# MainSch.net
KiCad netlist of a schematic drawn in Altium Designer
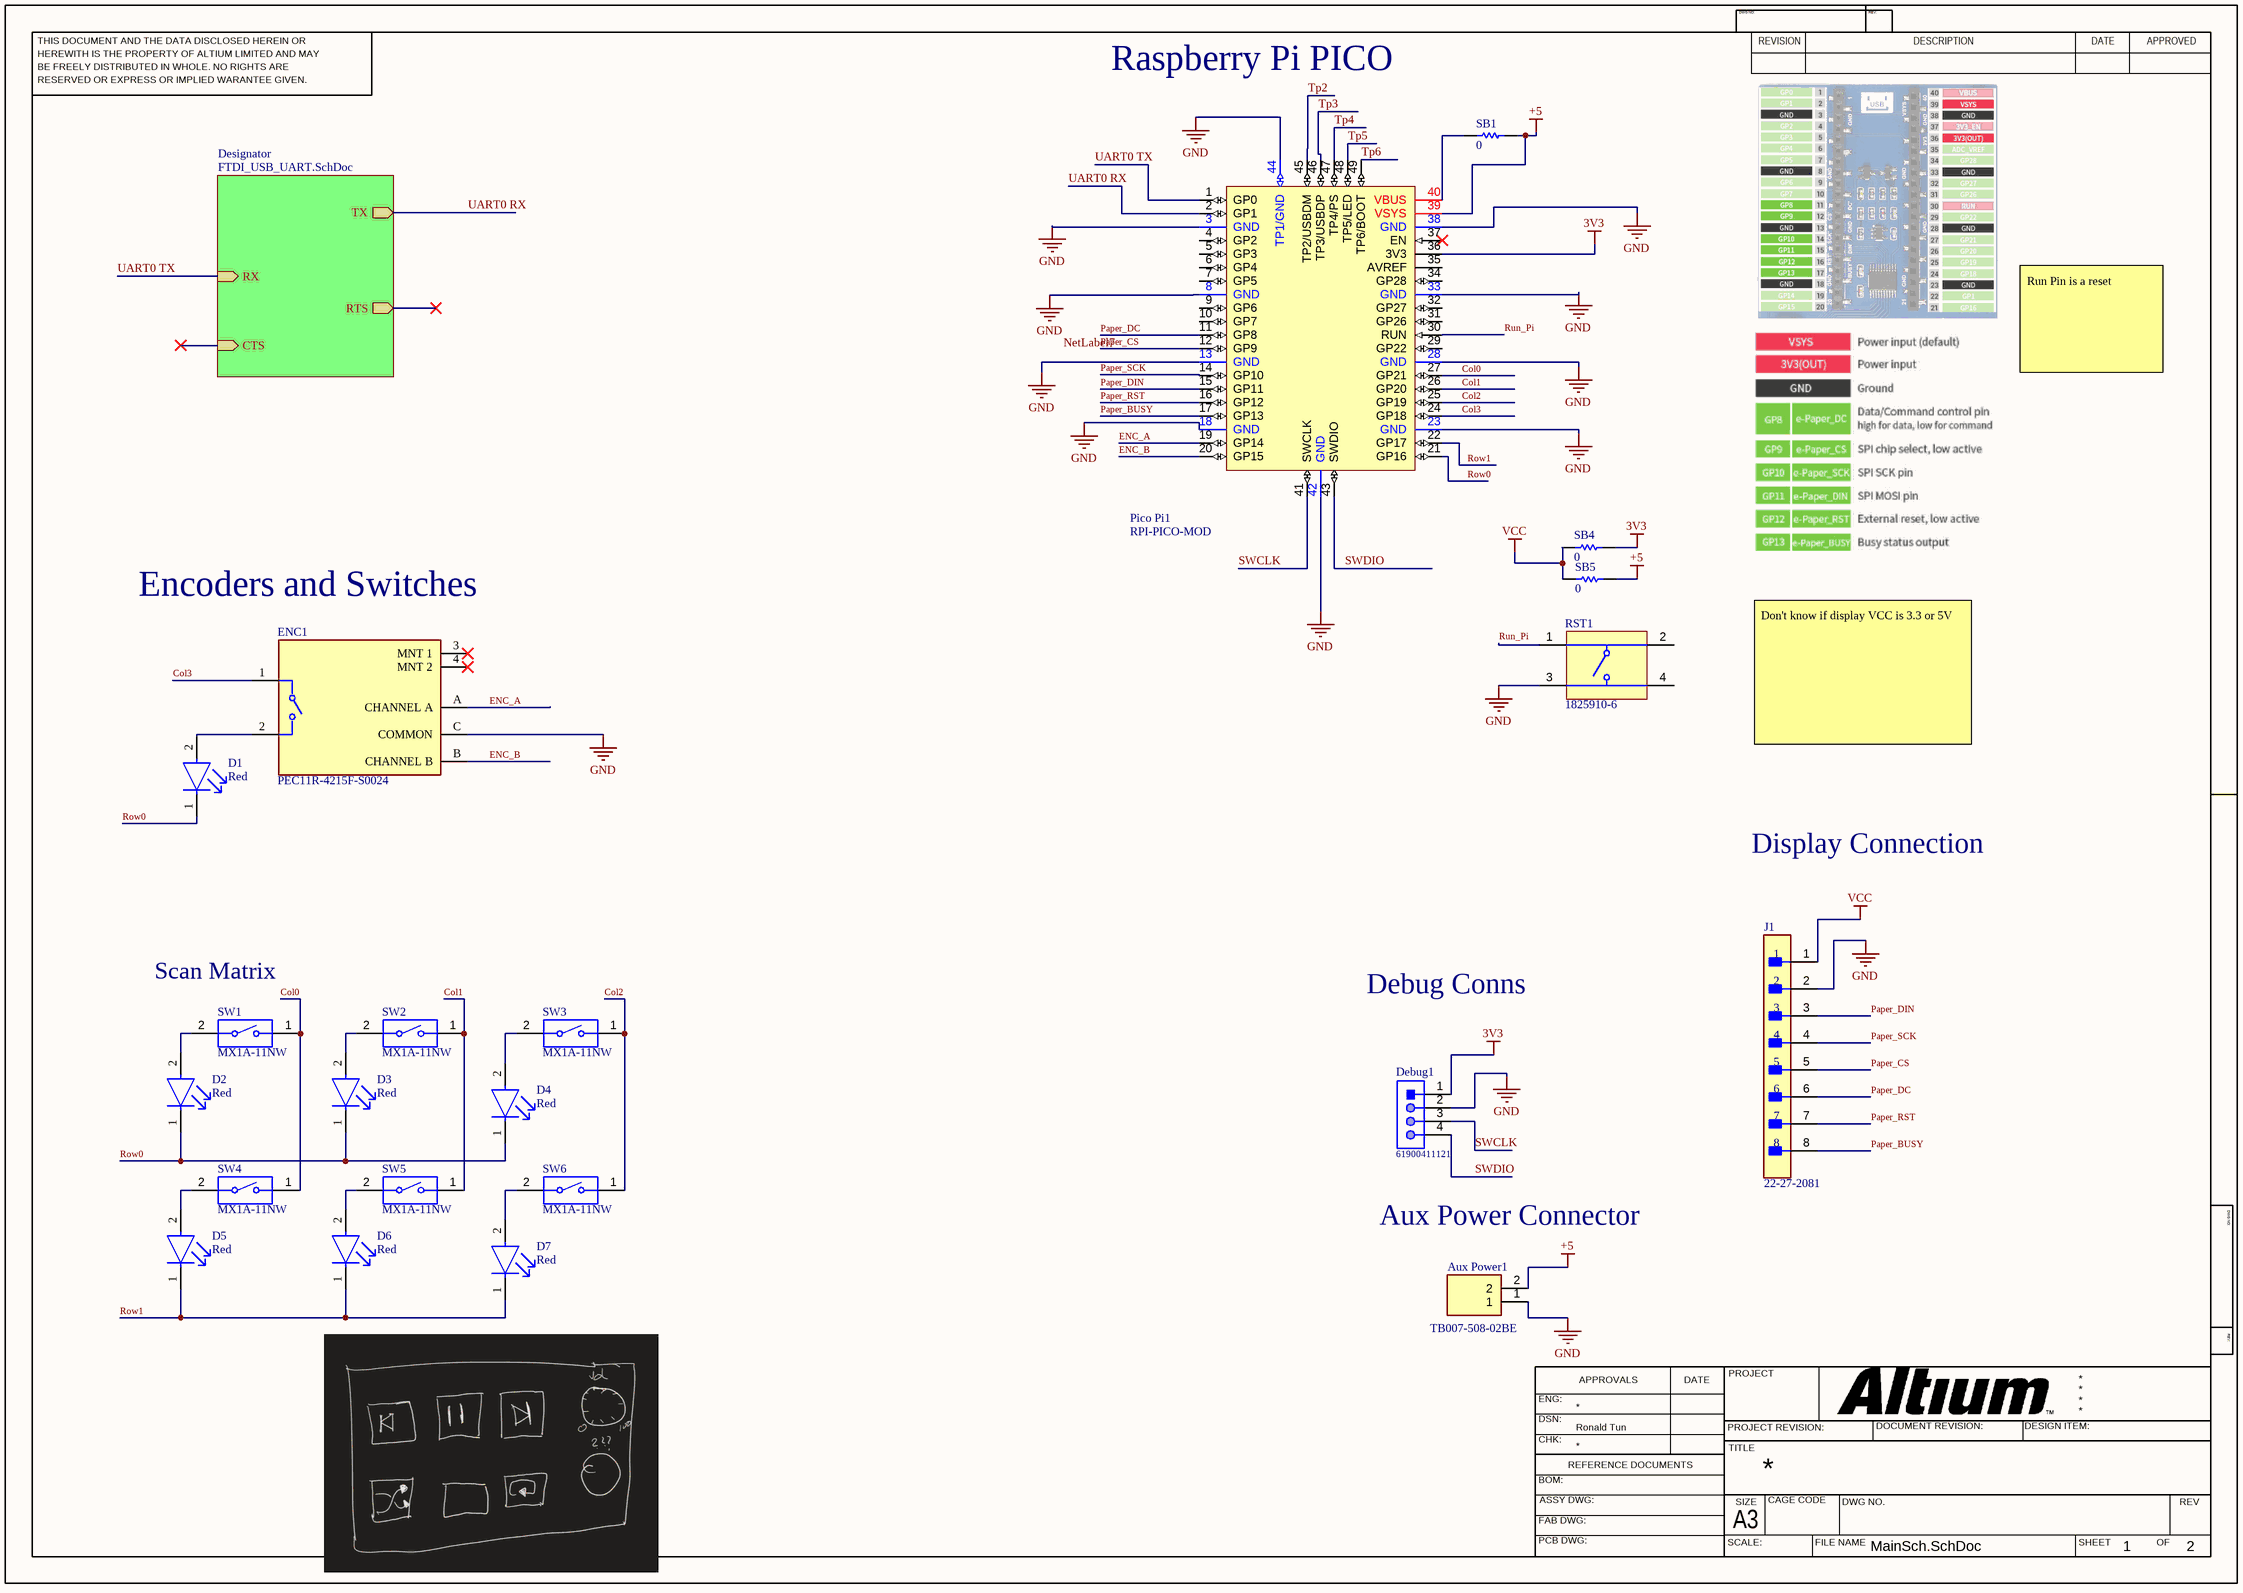
[diagram p0: MainSch.SchDoc]

(export (version "E")
  (design (tool "Eeschema 10.0.6"))
  (components
    (comp (ref "Aux Power1")
      (value "TB007-508-02BE")
      (footprint "SamacSys:TB00750802BE")
      (description "Connector")
      (fields (field (name "MOUSER PART NUMBER") "490-TB007-508-02BE"))
      (libsource (lib "SamacSys") (part "TB007-508-02BE"))
    )
    (comp (ref "D1")
      (value "Red")
      (footprint "FP-150080SS75000-MFG")
      (description "LED RED CLEAR 0805 SMD")
      (libsource (lib "Altium Content Vault") (part "8706943c75ba83719d021d2fdc84c58"))
    )
    (comp (ref "D2")
      (value "Red")
      (footprint "FP-150080SS75000-MFG")
      (description "LED RED CLEAR 0805 SMD")
      (libsource (lib "Altium Content Vault") (part "8706943c75ba83719d021d2fdc84c58"))
    )
    (comp (ref "D3")
      (value "Red")
      (footprint "FP-150080SS75000-MFG")
      (description "LED RED CLEAR 0805 SMD")
      (libsource (lib "Altium Content Vault") (part "8706943c75ba83719d021d2fdc84c58"))
    )
    (comp (ref "D4")
      (value "Red")
      (footprint "FP-150080SS75000-MFG")
      (description "LED RED CLEAR 0805 SMD")
      (libsource (lib "Altium Content Vault") (part "8706943c75ba83719d021d2fdc84c58"))
    )
    (comp (ref "D5")
      (value "Red")
      (footprint "FP-150080SS75000-MFG")
      (description "LED RED CLEAR 0805 SMD")
      (libsource (lib "Altium Content Vault") (part "8706943c75ba83719d021d2fdc84c58"))
    )
    (comp (ref "D6")
      (value "Red")
      (footprint "FP-150080SS75000-MFG")
      (description "LED RED CLEAR 0805 SMD")
      (libsource (lib "Altium Content Vault") (part "8706943c75ba83719d021d2fdc84c58"))
    )
    (comp (ref "D7")
      (value "Red")
      (footprint "FP-150080SS75000-MFG")
      (description "LED RED CLEAR 0805 SMD")
      (libsource (lib "Altium Content Vault") (part "8706943c75ba83719d021d2fdc84c58"))
    )
    (comp (ref "Debug1")
      (value "61900411121")
      (footprint "61900411121")
      (description "Male Locking Header WR-WTB, THT, Vertical, pitch 2.54 mm, 1 x 4 position")
      (fields (field (name "MANUFACTURER") "Wurth Elektronik") (field (name "PUBLISHER") "WurthElektronik"))
      (libsource (lib "Altium Content Vault") (part "WE-CN-1P-M-R4"))
    )
    (comp (ref "ENC1")
      (value "PEC11R-4215F-S0024")
      (footprint "FP-PEC11R-4215F-S0024-MFG")
      (description "ROTARY ENCODER MECHANICAL 24PPR")
      (libsource (lib "Altium Content Vault") (part "5f1dd25a4c49fa66e7eeb899730fe11"))
    )
    (comp (ref "J1")
      (value "22-27-2081")
      (footprint "FP-22-27-2081-MFG")
      (description "CONN HEADER VERT 8POS 2.54MM")
      (libsource (lib "Altium Content Vault") (part "99ec2b232beb5d2356d4d77f6a047f0"))
    )
    (comp (ref "Pico Pi1")
      (value "RPI-PICO-MOD")
      (footprint "RPI-PICO-MOD")
      (description "RASPBERRY PI PICO RP2040 BOARD")
      (fields
        (field (name "MANUFACTURER") "Raspberry Pi Foundation")
        (field (name "MANUFACTURER PART NO") "SC0915")
      )
      (libsource (lib "RPi_Pico") (part "RPI-PICO-MOD"))
    )
    (comp (ref "RST1")
      (value "1825910-6")
      (footprint "TECO-1825910-6_V")
      (description "Tact Switch, SPST-NO, 0.05 A, -35 to 85 degC, 4-Pin THD, RoHS, Bulk")
      (fields (field (name "MANUFACTURER") "TE Connectivity"))
      (libsource (lib "Altium Content Vault") (part "SW-SPST-4_A"))
    )
    (comp (ref "SB1")
      (value "0")
      (footprint "RESC1608X55X25ML10T15")
      (description "Chip Resistor, 0 Ohm, +/- 5%, 0.1 W, -55 to 155 degC, 0603 (1608 Metric), RoHS, Tape and Reel")
      (fields (field (name "TOLERANCE") "5%") (field (name "MANUFACTURER") "Yageo"))
      (libsource (lib "Altium Content Vault") (part "RES-2"))
    )
    (comp (ref "SB4")
      (value "0")
      (footprint "RESC1608X55X25ML10T15")
      (description "Chip Resistor, 0 Ohm, +/- 5%, 0.1 W, -55 to 155 degC, 0603 (1608 Metric), RoHS, Tape and Reel")
      (fields (field (name "TOLERANCE") "5%") (field (name "MANUFACTURER") "Yageo"))
      (libsource (lib "Altium Content Vault") (part "RES-2"))
    )
    (comp (ref "SB5")
      (value "0")
      (footprint "RESC1608X55X25ML10T15")
      (description "Chip Resistor, 0 Ohm, +/- 5%, 0.1 W, -55 to 155 degC, 0603 (1608 Metric), RoHS, Tape and Reel")
      (fields (field (name "TOLERANCE") "5%") (field (name "MANUFACTURER") "Yageo"))
      (libsource (lib "Altium Content Vault") (part "RES-2"))
    )
    (comp (ref "SW1")
      (value "MX1A-11NW")
      (footprint "CHRY-MX1A-11NW_V")
      (description "Keylock Switch, 12 V, -10 to 70 degC, 2-Pin THD, RoHS, Bulk")
      (fields (field (name "MANUFACTURER") "Cherry") (field (name "PART NO") "MX1A11NW"))
      (libsource (lib "Altium Content Vault") (part "KEYSW-SPST-2"))
    )
    (comp (ref "SW2")
      (value "MX1A-11NW")
      (footprint "CHRY-MX1A-11NW_V")
      (description "Keylock Switch, 12 V, -10 to 70 degC, 2-Pin THD, RoHS, Bulk")
      (fields (field (name "MANUFACTURER") "Cherry") (field (name "PART NO") "MX1A11NW"))
      (libsource (lib "Altium Content Vault") (part "KEYSW-SPST-2"))
    )
    (comp (ref "SW3")
      (value "MX1A-11NW")
      (footprint "CHRY-MX1A-11NW_V")
      (description "Keylock Switch, 12 V, -10 to 70 degC, 2-Pin THD, RoHS, Bulk")
      (fields (field (name "MANUFACTURER") "Cherry") (field (name "PART NO") "MX1A11NW"))
      (libsource (lib "Altium Content Vault") (part "KEYSW-SPST-2"))
    )
    (comp (ref "SW4")
      (value "MX1A-11NW")
      (footprint "CHRY-MX1A-11NW_V")
      (description "Keylock Switch, 12 V, -10 to 70 degC, 2-Pin THD, RoHS, Bulk")
      (fields (field (name "MANUFACTURER") "Cherry") (field (name "PART NO") "MX1A11NW"))
      (libsource (lib "Altium Content Vault") (part "KEYSW-SPST-2"))
    )
    (comp (ref "SW5")
      (value "MX1A-11NW")
      (footprint "CHRY-MX1A-11NW_V")
      (description "Keylock Switch, 12 V, -10 to 70 degC, 2-Pin THD, RoHS, Bulk")
      (fields (field (name "MANUFACTURER") "Cherry") (field (name "PART NO") "MX1A11NW"))
      (libsource (lib "Altium Content Vault") (part "KEYSW-SPST-2"))
    )
    (comp (ref "SW6")
      (value "MX1A-11NW")
      (footprint "CHRY-MX1A-11NW_V")
      (description "Keylock Switch, 12 V, -10 to 70 degC, 2-Pin THD, RoHS, Bulk")
      (fields (field (name "MANUFACTURER") "Cherry") (field (name "PART NO") "MX1A11NW"))
      (libsource (lib "Altium Content Vault") (part "KEYSW-SPST-2"))
    )
  )
  (nets
    (net (code "1") (name "+5") (class "Default")
      (node (ref "Aux Power1") (pin "2") (pinfunction "2_2") (pintype "passive"))
      (node (ref "Pico Pi1") (pin "39") (pinfunction "VSYS_39") (pintype "power_in"))
      (node (ref "SB1") (pin "1") (pinfunction "1_1") (pintype "passive"))
      (node (ref "SB5") (pin "1") (pinfunction "1_1") (pintype "passive"))
    )
    (net (code "3") (name "/Col0") (class "Default")
      (node (ref "Pico Pi1") (pin "27") (pinfunction "GP21_27") (pintype "bidirectional"))
      (node (ref "SW1") (pin "1") (pinfunction "1_1") (pintype "passive"))
      (node (ref "SW4") (pin "1") (pinfunction "1_1") (pintype "passive"))
    )
    (net (code "4") (name "/Col1") (class "Default")
      (node (ref "Pico Pi1") (pin "26") (pinfunction "GP20_26") (pintype "bidirectional"))
      (node (ref "SW2") (pin "1") (pinfunction "1_1") (pintype "passive"))
      (node (ref "SW5") (pin "1") (pinfunction "1_1") (pintype "passive"))
    )
    (net (code "5") (name "/Col2") (class "Default")
      (node (ref "Pico Pi1") (pin "25") (pinfunction "GP19_25") (pintype "bidirectional"))
      (node (ref "SW3") (pin "1") (pinfunction "1_1") (pintype "passive"))
      (node (ref "SW6") (pin "1") (pinfunction "1_1") (pintype "passive"))
    )
    (net (code "6") (name "/Col3") (class "Default")
      (node (ref "ENC1") (pin "1") (pinfunction "1_1") (pintype "passive"))
      (node (ref "Pico Pi1") (pin "24") (pinfunction "GP18_24") (pintype "bidirectional"))
    )
    (net (code "7") (name "/ENC_A") (class "Default")
      (node (ref "ENC1") (pin "A") (pinfunction "CHANNEL_A_A") (pintype "passive"))
      (node (ref "Pico Pi1") (pin "19") (pinfunction "GP14_19") (pintype "bidirectional"))
    )
    (net (code "8") (name "/ENC_B") (class "Default")
      (node (ref "ENC1") (pin "B") (pinfunction "CHANNEL_B_B") (pintype "passive"))
      (node (ref "Pico Pi1") (pin "20") (pinfunction "GP15_20") (pintype "bidirectional"))
    )
    (net (code "10") (name "/Paper_BUSY") (class "Default")
      (node (ref "J1") (pin "8") (pinfunction "8_8") (pintype "passive"))
      (node (ref "Pico Pi1") (pin "17") (pinfunction "GP13_17") (pintype "bidirectional"))
    )
    (net (code "11") (name "/Paper_CS") (class "Default")
      (node (ref "J1") (pin "5") (pinfunction "5_5") (pintype "passive"))
      (node (ref "Pico Pi1") (pin "12") (pinfunction "GP9_12") (pintype "bidirectional"))
    )
    (net (code "12") (name "/Paper_DC") (class "Default")
      (node (ref "J1") (pin "6") (pinfunction "6_6") (pintype "passive"))
      (node (ref "Pico Pi1") (pin "11") (pinfunction "GP8_11") (pintype "bidirectional"))
    )
    (net (code "13") (name "/Paper_DIN") (class "Default")
      (node (ref "J1") (pin "3") (pinfunction "3_3") (pintype "passive"))
      (node (ref "Pico Pi1") (pin "15") (pinfunction "GP11_15") (pintype "bidirectional"))
    )
    (net (code "14") (name "/Paper_RST") (class "Default")
      (node (ref "J1") (pin "7") (pinfunction "7_7") (pintype "passive"))
      (node (ref "Pico Pi1") (pin "16") (pinfunction "GP12_16") (pintype "bidirectional"))
    )
    (net (code "15") (name "/Paper_SCK") (class "Default")
      (node (ref "J1") (pin "4") (pinfunction "4_4") (pintype "passive"))
      (node (ref "Pico Pi1") (pin "14") (pinfunction "GP10_14") (pintype "bidirectional"))
    )
    (net (code "17") (name "/Row0") (class "Default")
      (node (ref "D1") (pin "1") (pinfunction "C_1") (pintype "passive"))
      (node (ref "D2") (pin "1") (pinfunction "C_1") (pintype "passive"))
      (node (ref "D3") (pin "1") (pinfunction "C_1") (pintype "passive"))
      (node (ref "D4") (pin "1") (pinfunction "C_1") (pintype "passive"))
      (node (ref "Pico Pi1") (pin "21") (pinfunction "GP16_21") (pintype "bidirectional"))
    )
    (net (code "18") (name "/Row1") (class "Default")
      (node (ref "D5") (pin "1") (pinfunction "C_1") (pintype "passive"))
      (node (ref "D6") (pin "1") (pinfunction "C_1") (pintype "passive"))
      (node (ref "D7") (pin "1") (pinfunction "C_1") (pintype "passive"))
      (node (ref "Pico Pi1") (pin "22") (pinfunction "GP17_22") (pintype "bidirectional"))
    )
    (net (code "19") (name "/Run_Pi") (class "Default")
      (node (ref "Pico Pi1") (pin "30") (pinfunction "RUN_30") (pintype "input"))
      (node (ref "RST1") (pin "1") (pinfunction "1_1") (pintype "passive"))
    )
    (net (code "20") (name "/SWCLK") (class "Default")
      (node (ref "Debug1") (pin "3") (pinfunction "3_3") (pintype "passive"))
      (node (ref "Pico Pi1") (pin "41") (pinfunction "SWCLK_41") (pintype "bidirectional"))
    )
    (net (code "21") (name "/SWDIO") (class "Default")
      (node (ref "Debug1") (pin "4") (pinfunction "4_4") (pintype "passive"))
      (node (ref "Pico Pi1") (pin "43") (pinfunction "SWDIO_43") (pintype "bidirectional"))
    )
    (net (code "22") (name "/Tp2") (class "Default")
      (node (ref "Pico Pi1") (pin "45") (pinfunction "TP2/USBDM_45") (pintype "bidirectional"))
    )
    (net (code "23") (name "/Tp3") (class "Default")
      (node (ref "Pico Pi1") (pin "46") (pinfunction "TP3/USBDP_46") (pintype "bidirectional"))
    )
    (net (code "24") (name "/Tp4") (class "Default")
      (node (ref "Pico Pi1") (pin "47") (pinfunction "TP4/PS_47") (pintype "bidirectional"))
    )
    (net (code "25") (name "/Tp5") (class "Default")
      (node (ref "Pico Pi1") (pin "48") (pinfunction "TP5/LED_48") (pintype "bidirectional"))
    )
    (net (code "26") (name "/Tp6") (class "Default")
      (node (ref "Pico Pi1") (pin "49") (pinfunction "TP6/BOOT_49") (pintype "bidirectional"))
    )
    (net (code "27") (name "/UART0 RX") (class "Default")
      (node (ref "Pico Pi1") (pin "2") (pinfunction "GP1_2") (pintype "bidirectional"))
    )
    (net (code "28") (name "/UART0 TX") (class "Default")
      (node (ref "Pico Pi1") (pin "1") (pinfunction "GP0_1") (pintype "bidirectional"))
    )
    (net (code "29") (name "3V3") (class "Default")
      (node (ref "Debug1") (pin "1") (pinfunction "1_1") (pintype "passive"))
      (node (ref "Pico Pi1") (pin "36") (pinfunction "3V3_36") (pintype "power_in"))
      (node (ref "SB4") (pin "1") (pinfunction "1_1") (pintype "passive"))
    )
    (net (code "30") (name "GND") (class "Default")
      (node (ref "Aux Power1") (pin "1") (pinfunction "1_1") (pintype "passive"))
      (node (ref "Debug1") (pin "2") (pinfunction "2_2") (pintype "passive"))
      (node (ref "ENC1") (pin "C") (pinfunction "COMMON_C") (pintype "passive"))
      (node (ref "J1") (pin "2") (pinfunction "2_2") (pintype "passive"))
      (node (ref "Pico Pi1") (pin "13") (pinfunction "GND_13") (pintype "power_in"))
      (node (ref "Pico Pi1") (pin "18") (pinfunction "GND_18") (pintype "power_in"))
      (node (ref "Pico Pi1") (pin "23") (pinfunction "GND_23") (pintype "power_in"))
      (node (ref "Pico Pi1") (pin "28") (pinfunction "GND_28") (pintype "power_in"))
      (node (ref "Pico Pi1") (pin "3") (pinfunction "GND_3") (pintype "power_in"))
      (node (ref "Pico Pi1") (pin "33") (pinfunction "GND_33") (pintype "power_in"))
      (node (ref "Pico Pi1") (pin "38") (pinfunction "GND_38") (pintype "power_in"))
      (node (ref "Pico Pi1") (pin "42") (pinfunction "GND_42") (pintype "power_in"))
      (node (ref "Pico Pi1") (pin "44") (pinfunction "TP1/GND_44") (pintype "bidirectional"))
      (node (ref "Pico Pi1") (pin "8") (pinfunction "GND_8") (pintype "power_in"))
      (node (ref "RST1") (pin "3") (pinfunction "3_3") (pintype "passive"))
    )
    (net (code "31") (name "Net-(D1-A)") (class "Default")
      (node (ref "D1") (pin "2") (pinfunction "A_2") (pintype "passive"))
      (node (ref "ENC1") (pin "2") (pinfunction "2_2") (pintype "passive"))
    )
    (net (code "32") (name "Net-(D2-A)") (class "Default")
      (node (ref "D2") (pin "2") (pinfunction "A_2") (pintype "passive"))
      (node (ref "SW1") (pin "2") (pinfunction "2_2") (pintype "passive"))
    )
    (net (code "33") (name "Net-(D3-A)") (class "Default")
      (node (ref "D3") (pin "2") (pinfunction "A_2") (pintype "passive"))
      (node (ref "SW2") (pin "2") (pinfunction "2_2") (pintype "passive"))
    )
    (net (code "34") (name "Net-(D4-A)") (class "Default")
      (node (ref "D4") (pin "2") (pinfunction "A_2") (pintype "passive"))
      (node (ref "SW3") (pin "2") (pinfunction "2_2") (pintype "passive"))
    )
    (net (code "35") (name "Net-(D5-A)") (class "Default")
      (node (ref "D5") (pin "2") (pinfunction "A_2") (pintype "passive"))
      (node (ref "SW4") (pin "2") (pinfunction "2_2") (pintype "passive"))
    )
    (net (code "36") (name "Net-(D6-A)") (class "Default")
      (node (ref "D6") (pin "2") (pinfunction "A_2") (pintype "passive"))
      (node (ref "SW5") (pin "2") (pinfunction "2_2") (pintype "passive"))
    )
    (net (code "37") (name "Net-(D7-A)") (class "Default")
      (node (ref "D7") (pin "2") (pinfunction "A_2") (pintype "passive"))
      (node (ref "SW6") (pin "2") (pinfunction "2_2") (pintype "passive"))
    )
    (net (code "38") (name "Net-(Pico Pi1-VBUS)") (class "Default")
      (node (ref "Pico Pi1") (pin "40") (pinfunction "VBUS_40") (pintype "power_in"))
      (node (ref "SB1") (pin "2") (pinfunction "2_2") (pintype "passive"))
    )
    (net (code "39") (name "VCC") (class "Default")
      (node (ref "J1") (pin "1") (pinfunction "1_1") (pintype "passive"))
      (node (ref "SB4") (pin "2") (pinfunction "2_2") (pintype "passive"))
      (node (ref "SB5") (pin "2") (pinfunction "2_2") (pintype "passive"))
    )
    (net (code "40") (name "unconnected-(ENC1-MNT_1-Pad3)") (class "Default")
      (node (ref "ENC1") (pin "3") (pinfunction "MNT_1_3") (pintype "passive+no_connect"))
    )
    (net (code "41") (name "unconnected-(ENC1-MNT_2-Pad4)") (class "Default")
      (node (ref "ENC1") (pin "4") (pinfunction "MNT_2_4") (pintype "passive+no_connect"))
    )
    (net (code "42") (name "unconnected-(Pico Pi1-AVREF-Pad35)") (class "Default")
      (node (ref "Pico Pi1") (pin "35") (pinfunction "AVREF_35") (pintype "power_in"))
    )
    (net (code "43") (name "unconnected-(Pico Pi1-EN-Pad37)") (class "Default")
      (node (ref "Pico Pi1") (pin "37") (pinfunction "EN_37") (pintype "input+no_connect"))
    )
    (net (code "44") (name "unconnected-(Pico Pi1-GP2-Pad4)") (class "Default")
      (node (ref "Pico Pi1") (pin "4") (pinfunction "GP2_4") (pintype "bidirectional"))
    )
    (net (code "45") (name "unconnected-(Pico Pi1-GP3-Pad5)") (class "Default")
      (node (ref "Pico Pi1") (pin "5") (pinfunction "GP3_5") (pintype "bidirectional"))
    )
    (net (code "46") (name "unconnected-(Pico Pi1-GP4-Pad6)") (class "Default")
      (node (ref "Pico Pi1") (pin "6") (pinfunction "GP4_6") (pintype "bidirectional"))
    )
    (net (code "47") (name "unconnected-(Pico Pi1-GP5-Pad7)") (class "Default")
      (node (ref "Pico Pi1") (pin "7") (pinfunction "GP5_7") (pintype "bidirectional"))
    )
    (net (code "48") (name "unconnected-(Pico Pi1-GP6-Pad9)") (class "Default")
      (node (ref "Pico Pi1") (pin "9") (pinfunction "GP6_9") (pintype "bidirectional"))
    )
    (net (code "49") (name "unconnected-(Pico Pi1-GP7-Pad10)") (class "Default")
      (node (ref "Pico Pi1") (pin "10") (pinfunction "GP7_10") (pintype "bidirectional"))
    )
    (net (code "50") (name "unconnected-(Pico Pi1-GP22-Pad29)") (class "Default")
      (node (ref "Pico Pi1") (pin "29") (pinfunction "GP22_29") (pintype "bidirectional"))
    )
    (net (code "51") (name "unconnected-(Pico Pi1-GP26-Pad31)") (class "Default")
      (node (ref "Pico Pi1") (pin "31") (pinfunction "GP26_31") (pintype "bidirectional"))
    )
    (net (code "52") (name "unconnected-(Pico Pi1-GP27-Pad32)") (class "Default")
      (node (ref "Pico Pi1") (pin "32") (pinfunction "GP27_32") (pintype "bidirectional"))
    )
    (net (code "53") (name "unconnected-(Pico Pi1-GP28-Pad34)") (class "Default")
      (node (ref "Pico Pi1") (pin "34") (pinfunction "GP28_34") (pintype "bidirectional"))
    )
    (net (code "54") (name "unconnected-(RST1-Pad2)") (class "Default")
      (node (ref "RST1") (pin "2") (pinfunction "2_2") (pintype "passive"))
    )
    (net (code "55") (name "unconnected-(RST1-Pad4)") (class "Default")
      (node (ref "RST1") (pin "4") (pinfunction "4_4") (pintype "passive"))
    )
  )
)
